# Output_Connector.net
KiCad netlist of a schematic drawn in Altium Designer
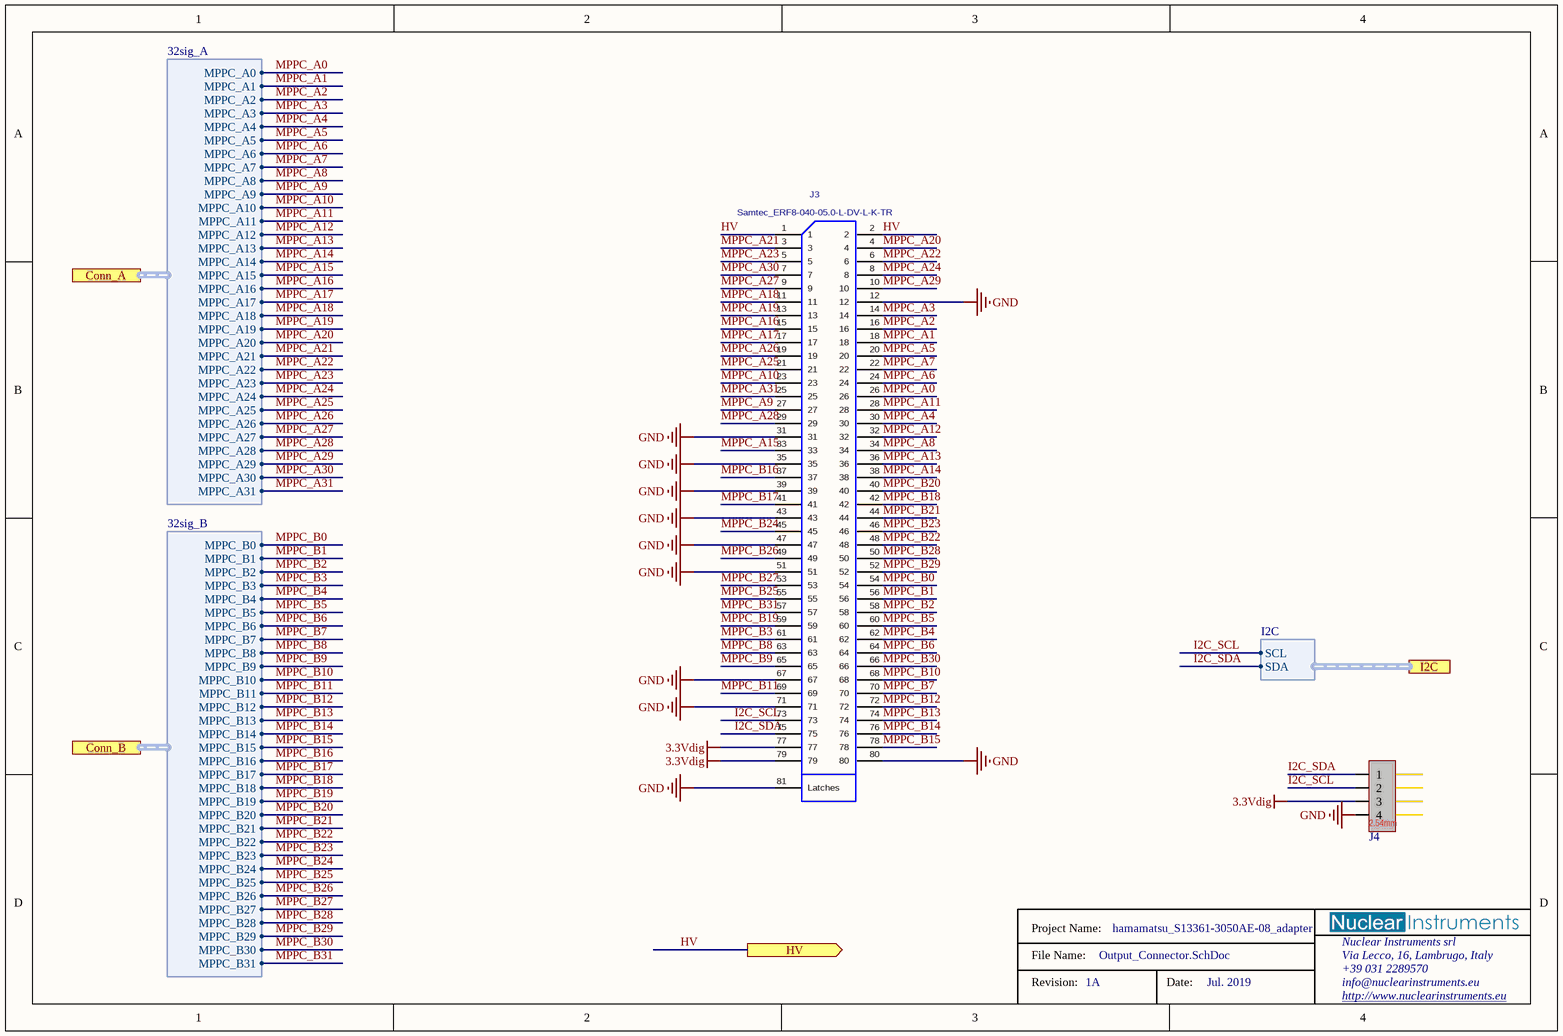
[diagram p0: Output_Connector.SchDoc]

(export (version "E")
  (design (tool "Eeschema 10.0.6"))
  (components
    (comp (ref "J3")
      (value "Samtec_ERF8-040-05.0-L-DV-L-K-TR")
      (footprint "Samtec_ERF8-040-05.0-L-DV-L-K-TR")
      (description "0.8mm Edge Rate Socket Assembly, Double Vertical Row, 40 Pins.")
      (libsource (lib "Board_Board_Connectors__SARAversion-51") (part "Samtec_ERF8-040-05.0-L-DV-L-K-TR"))
    )
    (comp (ref "J4")
      (value "4 way, 2.54mm pitch")
      (footprint "Wurth_WR-PHD_4way_2.54mm_male")
      (description "Male 4 way 2.54 mm")
      (libsource (lib "Strip_Connectors__SARAversion-22") (part "Wurth_WR-PHD_4way_2.54mm_male"))
    )
  )
  (nets
    (net (code "4") (name "/HV") (class "Default")
      (node (ref "J3") (pin "1") (pinfunction "1_1") (pintype "passive"))
      (node (ref "J3") (pin "2") (pinfunction "2_2") (pintype "passive"))
    )
    (net (code "5") (name "/I2C_SCL") (class "Default")
      (node (ref "J3") (pin "73") (pinfunction "73_73") (pintype "passive"))
      (node (ref "J4") (pin "2") (pinfunction "2_2") (pintype "passive"))
    )
    (net (code "6") (name "/I2C_SDA") (class "Default")
      (node (ref "J3") (pin "75") (pinfunction "75_75") (pintype "passive"))
      (node (ref "J4") (pin "1") (pinfunction "1_1") (pintype "passive"))
    )
    (net (code "7") (name "/MPPC_A0") (class "Default")
      (node (ref "J3") (pin "26") (pinfunction "26_26") (pintype "passive"))
    )
    (net (code "8") (name "/MPPC_A1") (class "Default")
      (node (ref "J3") (pin "18") (pinfunction "18_18") (pintype "passive"))
    )
    (net (code "9") (name "/MPPC_A2") (class "Default")
      (node (ref "J3") (pin "16") (pinfunction "16_16") (pintype "passive"))
    )
    (net (code "10") (name "/MPPC_A3") (class "Default")
      (node (ref "J3") (pin "14") (pinfunction "14_14") (pintype "passive"))
    )
    (net (code "11") (name "/MPPC_A4") (class "Default")
      (node (ref "J3") (pin "30") (pinfunction "30_30") (pintype "passive"))
    )
    (net (code "12") (name "/MPPC_A5") (class "Default")
      (node (ref "J3") (pin "20") (pinfunction "20_20") (pintype "passive"))
    )
    (net (code "13") (name "/MPPC_A6") (class "Default")
      (node (ref "J3") (pin "24") (pinfunction "24_24") (pintype "passive"))
    )
    (net (code "14") (name "/MPPC_A7") (class "Default")
      (node (ref "J3") (pin "22") (pinfunction "22_22") (pintype "passive"))
    )
    (net (code "15") (name "/MPPC_A8") (class "Default")
      (node (ref "J3") (pin "34") (pinfunction "34_34") (pintype "passive"))
    )
    (net (code "16") (name "/MPPC_A9") (class "Default")
      (node (ref "J3") (pin "27") (pinfunction "27_27") (pintype "passive"))
    )
    (net (code "17") (name "/MPPC_A10") (class "Default")
      (node (ref "J3") (pin "23") (pinfunction "23_23") (pintype "passive"))
    )
    (net (code "18") (name "/MPPC_A11") (class "Default")
      (node (ref "J3") (pin "28") (pinfunction "28_28") (pintype "passive"))
    )
    (net (code "19") (name "/MPPC_A12") (class "Default")
      (node (ref "J3") (pin "32") (pinfunction "32_32") (pintype "passive"))
    )
    (net (code "20") (name "/MPPC_A13") (class "Default")
      (node (ref "J3") (pin "36") (pinfunction "36_36") (pintype "passive"))
    )
    (net (code "21") (name "/MPPC_A14") (class "Default")
      (node (ref "J3") (pin "38") (pinfunction "38_38") (pintype "passive"))
    )
    (net (code "22") (name "/MPPC_A15") (class "Default")
      (node (ref "J3") (pin "33") (pinfunction "33_33") (pintype "passive"))
    )
    (net (code "23") (name "/MPPC_A16") (class "Default")
      (node (ref "J3") (pin "15") (pinfunction "15_15") (pintype "passive"))
    )
    (net (code "24") (name "/MPPC_A17") (class "Default")
      (node (ref "J3") (pin "17") (pinfunction "17_17") (pintype "passive"))
    )
    (net (code "25") (name "/MPPC_A18") (class "Default")
      (node (ref "J3") (pin "11") (pinfunction "11_11") (pintype "passive"))
    )
    (net (code "26") (name "/MPPC_A19") (class "Default")
      (node (ref "J3") (pin "13") (pinfunction "13_13") (pintype "passive"))
    )
    (net (code "27") (name "/MPPC_A20") (class "Default")
      (node (ref "J3") (pin "4") (pinfunction "4_4") (pintype "passive"))
    )
    (net (code "28") (name "/MPPC_A21") (class "Default")
      (node (ref "J3") (pin "3") (pinfunction "3_3") (pintype "passive"))
    )
    (net (code "29") (name "/MPPC_A22") (class "Default")
      (node (ref "J3") (pin "6") (pinfunction "6_6") (pintype "passive"))
    )
    (net (code "30") (name "/MPPC_A23") (class "Default")
      (node (ref "J3") (pin "5") (pinfunction "5_5") (pintype "passive"))
    )
    (net (code "31") (name "/MPPC_A24") (class "Default")
      (node (ref "J3") (pin "8") (pinfunction "8_8") (pintype "passive"))
    )
    (net (code "32") (name "/MPPC_A25") (class "Default")
      (node (ref "J3") (pin "21") (pinfunction "21_21") (pintype "passive"))
    )
    (net (code "33") (name "/MPPC_A26") (class "Default")
      (node (ref "J3") (pin "19") (pinfunction "19_19") (pintype "passive"))
    )
    (net (code "34") (name "/MPPC_A27") (class "Default")
      (node (ref "J3") (pin "9") (pinfunction "9_9") (pintype "passive"))
    )
    (net (code "35") (name "/MPPC_A28") (class "Default")
      (node (ref "J3") (pin "29") (pinfunction "29_29") (pintype "passive"))
    )
    (net (code "36") (name "/MPPC_A29") (class "Default")
      (node (ref "J3") (pin "10") (pinfunction "10_10") (pintype "passive"))
    )
    (net (code "37") (name "/MPPC_A30") (class "Default")
      (node (ref "J3") (pin "7") (pinfunction "7_7") (pintype "passive"))
    )
    (net (code "38") (name "/MPPC_A31") (class "Default")
      (node (ref "J3") (pin "25") (pinfunction "25_25") (pintype "passive"))
    )
    (net (code "39") (name "/MPPC_B0") (class "Default")
      (node (ref "J3") (pin "54") (pinfunction "54_54") (pintype "passive"))
    )
    (net (code "40") (name "/MPPC_B1") (class "Default")
      (node (ref "J3") (pin "56") (pinfunction "56_56") (pintype "passive"))
    )
    (net (code "41") (name "/MPPC_B2") (class "Default")
      (node (ref "J3") (pin "58") (pinfunction "58_58") (pintype "passive"))
    )
    (net (code "42") (name "/MPPC_B3") (class "Default")
      (node (ref "J3") (pin "61") (pinfunction "61_61") (pintype "passive"))
    )
    (net (code "43") (name "/MPPC_B4") (class "Default")
      (node (ref "J3") (pin "62") (pinfunction "62_62") (pintype "passive"))
    )
    (net (code "44") (name "/MPPC_B5") (class "Default")
      (node (ref "J3") (pin "60") (pinfunction "60_60") (pintype "passive"))
    )
    (net (code "45") (name "/MPPC_B6") (class "Default")
      (node (ref "J3") (pin "64") (pinfunction "64_64") (pintype "passive"))
    )
    (net (code "46") (name "/MPPC_B7") (class "Default")
      (node (ref "J3") (pin "70") (pinfunction "70_70") (pintype "passive"))
    )
    (net (code "47") (name "/MPPC_B8") (class "Default")
      (node (ref "J3") (pin "63") (pinfunction "63_63") (pintype "passive"))
    )
    (net (code "48") (name "/MPPC_B9") (class "Default")
      (node (ref "J3") (pin "65") (pinfunction "65_65") (pintype "passive"))
    )
    (net (code "49") (name "/MPPC_B10") (class "Default")
      (node (ref "J3") (pin "68") (pinfunction "68_68") (pintype "passive"))
    )
    (net (code "50") (name "/MPPC_B11") (class "Default")
      (node (ref "J3") (pin "69") (pinfunction "69_69") (pintype "passive"))
    )
    (net (code "51") (name "/MPPC_B12") (class "Default")
      (node (ref "J3") (pin "72") (pinfunction "72_72") (pintype "passive"))
    )
    (net (code "52") (name "/MPPC_B13") (class "Default")
      (node (ref "J3") (pin "74") (pinfunction "74_74") (pintype "passive"))
    )
    (net (code "53") (name "/MPPC_B14") (class "Default")
      (node (ref "J3") (pin "76") (pinfunction "76_76") (pintype "passive"))
    )
    (net (code "54") (name "/MPPC_B15") (class "Default")
      (node (ref "J3") (pin "78") (pinfunction "78_78") (pintype "passive"))
    )
    (net (code "55") (name "/MPPC_B16") (class "Default")
      (node (ref "J3") (pin "37") (pinfunction "37_37") (pintype "passive"))
    )
    (net (code "56") (name "/MPPC_B17") (class "Default")
      (node (ref "J3") (pin "41") (pinfunction "41_41") (pintype "passive"))
    )
    (net (code "57") (name "/MPPC_B18") (class "Default")
      (node (ref "J3") (pin "42") (pinfunction "42_42") (pintype "passive"))
    )
    (net (code "58") (name "/MPPC_B19") (class "Default")
      (node (ref "J3") (pin "59") (pinfunction "59_59") (pintype "passive"))
    )
    (net (code "59") (name "/MPPC_B20") (class "Default")
      (node (ref "J3") (pin "40") (pinfunction "40_40") (pintype "passive"))
    )
    (net (code "60") (name "/MPPC_B21") (class "Default")
      (node (ref "J3") (pin "44") (pinfunction "44_44") (pintype "passive"))
    )
    (net (code "61") (name "/MPPC_B22") (class "Default")
      (node (ref "J3") (pin "48") (pinfunction "48_48") (pintype "passive"))
    )
    (net (code "62") (name "/MPPC_B23") (class "Default")
      (node (ref "J3") (pin "46") (pinfunction "46_46") (pintype "passive"))
    )
    (net (code "63") (name "/MPPC_B24") (class "Default")
      (node (ref "J3") (pin "45") (pinfunction "45_45") (pintype "passive"))
    )
    (net (code "64") (name "/MPPC_B25") (class "Default")
      (node (ref "J3") (pin "55") (pinfunction "55_55") (pintype "passive"))
    )
    (net (code "65") (name "/MPPC_B26") (class "Default")
      (node (ref "J3") (pin "49") (pinfunction "49_49") (pintype "passive"))
    )
    (net (code "66") (name "/MPPC_B27") (class "Default")
      (node (ref "J3") (pin "53") (pinfunction "53_53") (pintype "passive"))
    )
    (net (code "67") (name "/MPPC_B28") (class "Default")
      (node (ref "J3") (pin "50") (pinfunction "50_50") (pintype "passive"))
    )
    (net (code "68") (name "/MPPC_B29") (class "Default")
      (node (ref "J3") (pin "52") (pinfunction "52_52") (pintype "passive"))
    )
    (net (code "69") (name "/MPPC_B30") (class "Default")
      (node (ref "J3") (pin "66") (pinfunction "66_66") (pintype "passive"))
    )
    (net (code "70") (name "/MPPC_B31") (class "Default")
      (node (ref "J3") (pin "57") (pinfunction "57_57") (pintype "passive"))
    )
    (net (code "74") (name "3.3Vdig") (class "Default")
      (node (ref "J3") (pin "77") (pinfunction "77_77") (pintype "passive"))
      (node (ref "J3") (pin "79") (pinfunction "79_79") (pintype "passive"))
      (node (ref "J4") (pin "3") (pinfunction "3_3") (pintype "passive"))
    )
    (net (code "75") (name "GND") (class "Default")
      (node (ref "J3") (pin "12") (pinfunction "12_12") (pintype "passive"))
      (node (ref "J3") (pin "31") (pinfunction "31_31") (pintype "passive"))
      (node (ref "J3") (pin "35") (pinfunction "35_35") (pintype "passive"))
      (node (ref "J3") (pin "39") (pinfunction "39_39") (pintype "passive"))
      (node (ref "J3") (pin "43") (pinfunction "43_43") (pintype "passive"))
      (node (ref "J3") (pin "47") (pinfunction "47_47") (pintype "passive"))
      (node (ref "J3") (pin "51") (pinfunction "51_51") (pintype "passive"))
      (node (ref "J3") (pin "67") (pinfunction "67_67") (pintype "passive"))
      (node (ref "J3") (pin "71") (pinfunction "71_71") (pintype "passive"))
      (node (ref "J3") (pin "80") (pinfunction "80_80") (pintype "passive"))
      (node (ref "J3") (pin "81") (pinfunction "Latches_81") (pintype "passive"))
      (node (ref "J4") (pin "4") (pinfunction "4_4") (pintype "passive"))
    )
  )
)
